# AvionicsTestType.net
KiCad netlist of a schematic drawn in EAGLE
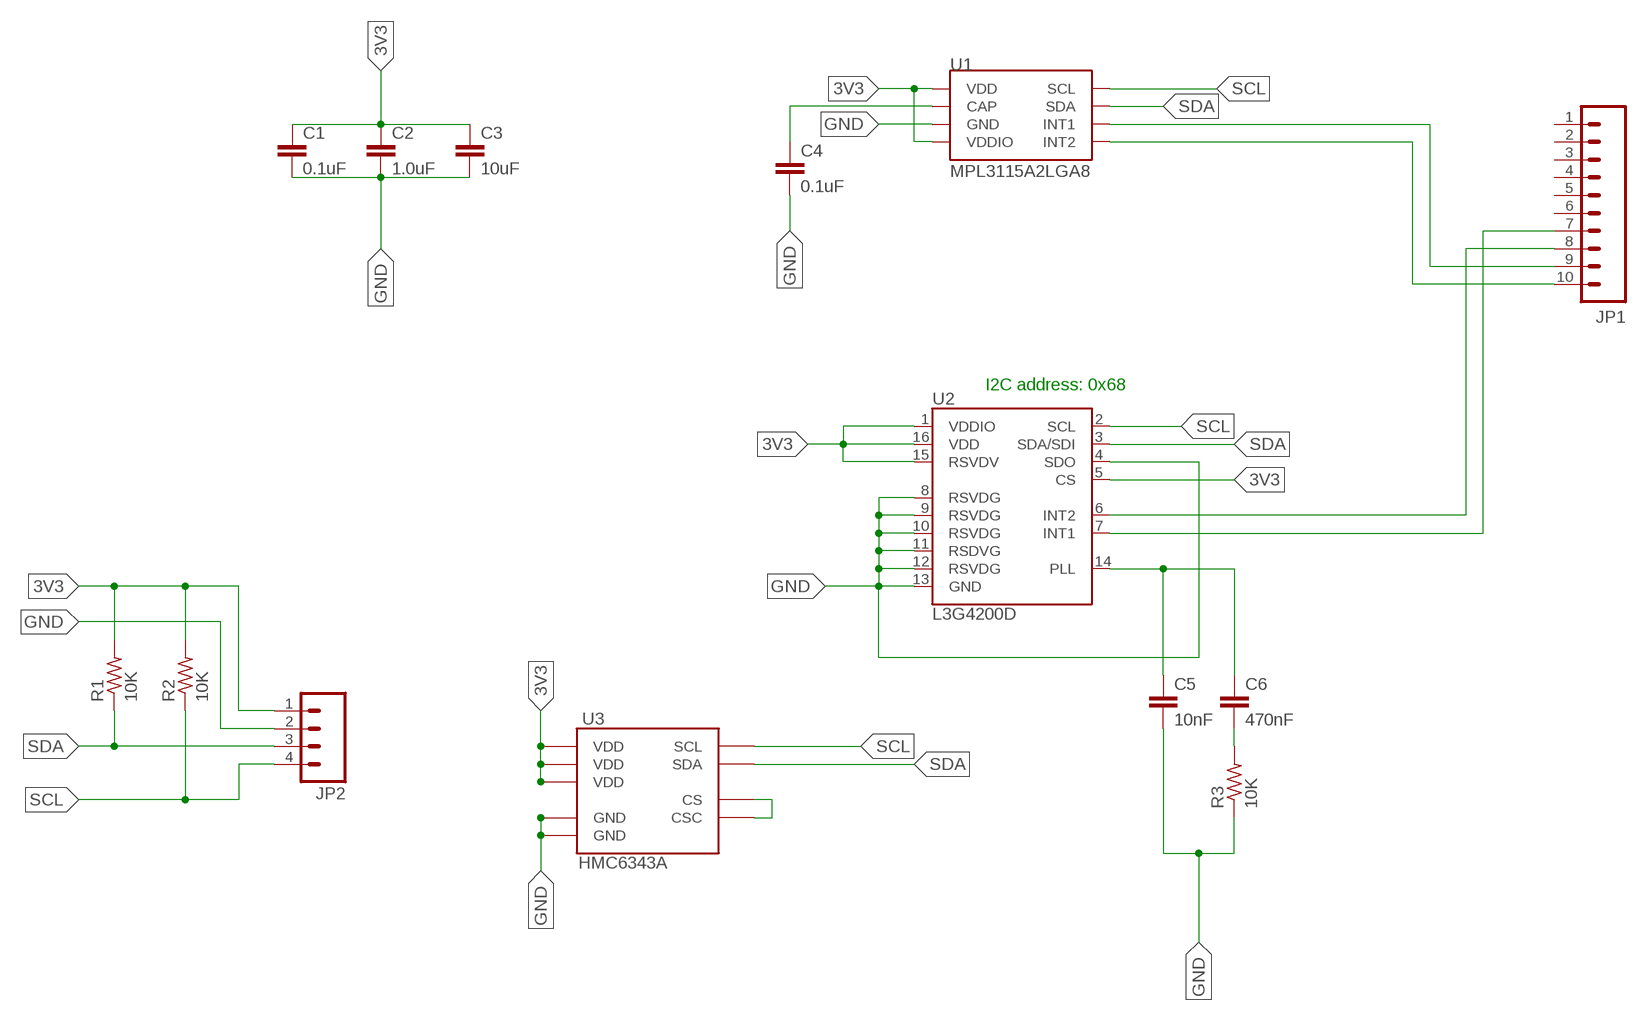
[diagram p0: schematic, sheet 1]

(export (version "E")
  (design (tool "Eeschema 10.0.6"))
  (components
    (comp (ref "C1")
      (value "0.1uF")
      (footprint "eagle-import:0603-CAP")
      (libsource (lib "eagle-import") (part "0.1UF-25V(+80/-20%)(0603)"))
    )
    (comp (ref "C2")
      (value "1.0uF")
      (footprint "eagle-import:0805-CAP")
      (libsource (lib "eagle-import") (part "1.0UF-25V-+80/-20(0805){dblquote}"))
    )
    (comp (ref "C3")
      (value "10uF")
      (footprint "eagle-import:0805-CAP")
      (libsource (lib "eagle-import") (part "1.0UF-25V-+80/-20(0805){dblquote}"))
    )
    (comp (ref "C4")
      (value "0.1uF")
      (footprint "eagle-import:0805-CAP")
      (libsource (lib "eagle-import") (part "1.0UF-25V-+80/-20(0805){dblquote}"))
    )
    (comp (ref "C5")
      (value "10nF")
      (footprint "eagle-import:0805-CAP")
      (libsource (lib "eagle-import") (part "1.0UF-25V-+80/-20(0805){dblquote}"))
    )
    (comp (ref "C6")
      (value "470nF")
      (footprint "eagle-import:0805-CAP")
      (libsource (lib "eagle-import") (part "1.0UF-25V-+80/-20(0805){dblquote}"))
    )
    (comp (ref "JP1")
      (value "M10LOCK")
      (footprint "eagle-import:1X10_LOCK")
      (libsource (lib "eagle-import") (part "M10LOCK"))
    )
    (comp (ref "JP2")
      (value "M04LOCK")
      (footprint "eagle-import:1X04_LOCK")
      (libsource (lib "eagle-import") (part "M04LOCK"))
    )
    (comp (ref "R1")
      (value "10K")
      (footprint "eagle-import:M0805")
      (libsource (lib "eagle-import") (part "R-US_M0805"))
    )
    (comp (ref "R2")
      (value "10K")
      (footprint "eagle-import:M0805")
      (libsource (lib "eagle-import") (part "R-US_M0805"))
    )
    (comp (ref "R3")
      (value "10K")
      (footprint "eagle-import:R0805")
      (libsource (lib "eagle-import") (part "R-US_R0805"))
    )
    (comp (ref "U1")
      (value "MPL3115A2LGA8")
      (footprint "eagle-import:LGA8")
      (libsource (lib "eagle-import") (part "MPL3115A2LGA8"))
    )
    (comp (ref "U2")
      (value "L3G4200D")
      (footprint "eagle-import:LGA16-4X4")
      (libsource (lib "eagle-import") (part "L3G4200D"))
    )
    (comp (ref "U3")
      (value "HMC6343A")
      (footprint "eagle-import:LCC36")
      (libsource (lib "eagle-import") (part "HMC6343A"))
    )
  )
  (nets
    (net (code "1") (name "3V3") (class "Default")
      (node (ref "C1") (pin "1") (pinfunction "1_1") (pintype "passive"))
      (node (ref "C2") (pin "1") (pinfunction "1_1") (pintype "passive"))
      (node (ref "C3") (pin "1") (pinfunction "1_1") (pintype "passive"))
      (node (ref "JP2") (pin "1") (pinfunction "1_1") (pintype "passive"))
      (node (ref "R1") (pin "2") (pinfunction "2_2") (pintype "passive"))
      (node (ref "R2") (pin "2") (pinfunction "2_2") (pintype "passive"))
      (node (ref "U1") (pin "1") (pinfunction "VDD_1") (pintype "power_in"))
      (node (ref "U1") (pin "4") (pinfunction "VDDIO_4") (pintype "power_in"))
      (node (ref "U2") (pin "1") (pinfunction "VDDIO_1") (pintype "bidirectional"))
      (node (ref "U2") (pin "15") (pinfunction "RSVDV_15") (pintype "bidirectional"))
      (node (ref "U2") (pin "16") (pinfunction "VDD_16") (pintype "bidirectional"))
      (node (ref "U2") (pin "5") (pinfunction "CS_5") (pintype "bidirectional"))
      (node (ref "U3") (pin "11") (pinfunction "VDD_11") (pintype "bidirectional"))
      (node (ref "U3") (pin "21") (pinfunction "VDD_21") (pintype "bidirectional"))
      (node (ref "U3") (pin "3") (pinfunction "VDD_3") (pintype "bidirectional"))
    )
    (net (code "2") (name "GND") (class "Default")
      (node (ref "C1") (pin "2") (pinfunction "2_2") (pintype "passive"))
      (node (ref "C2") (pin "2") (pinfunction "2_2") (pintype "passive"))
      (node (ref "C3") (pin "2") (pinfunction "2_2") (pintype "passive"))
      (node (ref "C4") (pin "2") (pinfunction "2_2") (pintype "passive"))
      (node (ref "C5") (pin "2") (pinfunction "2_2") (pintype "passive"))
      (node (ref "JP2") (pin "2") (pinfunction "2_2") (pintype "passive"))
      (node (ref "R3") (pin "1") (pinfunction "1_1") (pintype "passive"))
      (node (ref "U1") (pin "3") (pinfunction "GND_3") (pintype "power_in"))
      (node (ref "U2") (pin "10") (pinfunction "RSVDG_10") (pintype "bidirectional"))
      (node (ref "U2") (pin "11") (pinfunction "RSDVG_11") (pintype "bidirectional"))
      (node (ref "U2") (pin "12") (pinfunction "RSVDG_12") (pintype "bidirectional"))
      (node (ref "U2") (pin "13") (pinfunction "GND_13") (pintype "bidirectional"))
      (node (ref "U2") (pin "4") (pinfunction "SDO_4") (pintype "bidirectional"))
      (node (ref "U2") (pin "8") (pinfunction "RSVDG_8") (pintype "bidirectional"))
      (node (ref "U2") (pin "9") (pinfunction "RSVDG_9") (pintype "bidirectional"))
      (node (ref "U3") (pin "25") (pinfunction "GND_25") (pintype "bidirectional"))
      (node (ref "U3") (pin "29") (pinfunction "GND_29") (pintype "bidirectional"))
    )
    (net (code "3") (name "Net-(C6-Pad2)") (class "Default")
      (node (ref "C6") (pin "2") (pinfunction "2_2") (pintype "passive"))
      (node (ref "R3") (pin "2") (pinfunction "2_2") (pintype "passive"))
    )
    (net (code "4") (name "Net-(U1-CAP)") (class "Default")
      (node (ref "C4") (pin "1") (pinfunction "1_1") (pintype "passive"))
      (node (ref "U1") (pin "2") (pinfunction "CAP_2") (pintype "power_in"))
    )
    (net (code "5") (name "Net-(U1-INT1)") (class "Default")
      (node (ref "JP1") (pin "9") (pinfunction "9_9") (pintype "passive"))
      (node (ref "U1") (pin "6") (pinfunction "INT1_6") (pintype "output"))
    )
    (net (code "6") (name "Net-(U1-INT2)") (class "Default")
      (node (ref "JP1") (pin "10") (pinfunction "10_10") (pintype "passive"))
      (node (ref "U1") (pin "5") (pinfunction "INT2_5") (pintype "output"))
    )
    (net (code "7") (name "Net-(U2-INT1)") (class "Default")
      (node (ref "JP1") (pin "7") (pinfunction "7_7") (pintype "passive"))
      (node (ref "U2") (pin "7") (pinfunction "INT1_7") (pintype "bidirectional"))
    )
    (net (code "8") (name "Net-(U2-INT2)") (class "Default")
      (node (ref "JP1") (pin "8") (pinfunction "8_8") (pintype "passive"))
      (node (ref "U2") (pin "6") (pinfunction "INT2_6") (pintype "bidirectional"))
    )
    (net (code "9") (name "Net-(U2-PLL)") (class "Default")
      (node (ref "C5") (pin "1") (pinfunction "1_1") (pintype "passive"))
      (node (ref "C6") (pin "1") (pinfunction "1_1") (pintype "passive"))
      (node (ref "U2") (pin "14") (pinfunction "PLL_14") (pintype "bidirectional"))
    )
    (net (code "10") (name "Net-(U3-CS)") (class "Default")
      (node (ref "U3") (pin "22") (pinfunction "CS_22") (pintype "bidirectional"))
      (node (ref "U3") (pin "35") (pinfunction "CSC_35") (pintype "bidirectional"))
    )
    (net (code "11") (name "SCL") (class "Default")
      (node (ref "JP2") (pin "4") (pinfunction "4_4") (pintype "passive"))
      (node (ref "R2") (pin "1") (pinfunction "1_1") (pintype "passive"))
      (node (ref "U1") (pin "8") (pinfunction "SCL_8") (pintype "bidirectional"))
      (node (ref "U2") (pin "2") (pinfunction "SCL_2") (pintype "bidirectional"))
      (node (ref "U3") (pin "32") (pinfunction "SCL_32") (pintype "bidirectional"))
    )
    (net (code "12") (name "SDA") (class "Default")
      (node (ref "JP2") (pin "3") (pinfunction "3_3") (pintype "passive"))
      (node (ref "R1") (pin "1") (pinfunction "1_1") (pintype "passive"))
      (node (ref "U1") (pin "7") (pinfunction "SDA_7") (pintype "bidirectional"))
      (node (ref "U2") (pin "3") (pinfunction "SDA/SDI_3") (pintype "bidirectional"))
      (node (ref "U3") (pin "36") (pinfunction "SDA_36") (pintype "bidirectional"))
    )
    (net (code "13") (name "unconnected-(JP1-Pad1)") (class "Default")
      (node (ref "JP1") (pin "1") (pinfunction "1_1") (pintype "passive"))
    )
    (net (code "14") (name "unconnected-(JP1-Pad2)") (class "Default")
      (node (ref "JP1") (pin "2") (pinfunction "2_2") (pintype "passive"))
    )
    (net (code "15") (name "unconnected-(JP1-Pad3)") (class "Default")
      (node (ref "JP1") (pin "3") (pinfunction "3_3") (pintype "passive"))
    )
    (net (code "16") (name "unconnected-(JP1-Pad4)") (class "Default")
      (node (ref "JP1") (pin "4") (pinfunction "4_4") (pintype "passive"))
    )
    (net (code "17") (name "unconnected-(JP1-Pad5)") (class "Default")
      (node (ref "JP1") (pin "5") (pinfunction "5_5") (pintype "passive"))
    )
    (net (code "18") (name "unconnected-(JP1-Pad6)") (class "Default")
      (node (ref "JP1") (pin "6") (pinfunction "6_6") (pintype "passive"))
    )
  )
)
